# Sheet1.net
KiCad netlist of a schematic drawn in Altium Designer
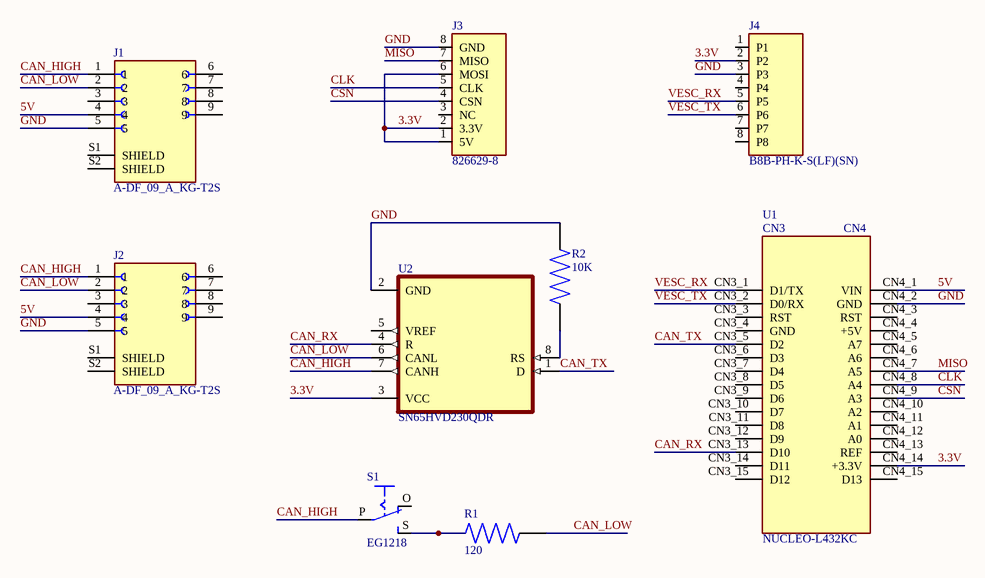
[diagram p0: Sheet1.SchDoc]

(export (version "E")
  (design (tool "Eeschema 10.0.6"))
  (components
    (comp (ref "J1")
      (value "A-DF_09_A_KG-T2S")
      (footprint "ASSMANN_A-DF_09_A_KG-T2S")
      (description "9 Position D-Sub Receptacle, Female Sockets Connector")
      (fields (field (name "MF") "Assmann WSW") (field (name "MP") "A-DF 09 A/KG-T2S"))
      (libsource (lib "A-DF_09_A_KG-T2S") (part "A-DF_09_A_KG-T2S"))
    )
    (comp (ref "J2")
      (value "A-DF_09_A_KG-T2S")
      (footprint "ASSMANN_A-DF_09_A_KG-T2S")
      (description "9 Position D-Sub Receptacle, Female Sockets Connector")
      (fields (field (name "MF") "Assmann WSW") (field (name "MP") "A-DF 09 A/KG-T2S"))
      (libsource (lib "A-DF_09_A_KG-T2S") (part "A-DF_09_A_KG-T2S"))
    )
    (comp (ref "J3")
      (value "826629-8")
      (footprint "TE_826629-8")
      (description "Conn Unshrouded Header HDR 8 POS 2.54mm Solder ST Thru-Hole Automotive Box")
      (fields (field (name "MF") "TE Connectivity"))
      (libsource (lib "826629-8") (part "826629-8"))
    )
    (comp (ref "J4")
      (value "B8B-PH-K-S(LF)(SN)")
      (footprint "SnapEDApcb:JST_B8B-PH-K-S(LF)(SN)")
      (description "Connector Header Through Hole 8 position 0.079 _2.00mm_")
      (fields (field (name "MF") "JST Sales") (field (name "MP") "B8B-PH-K-S_LF__SN_"))
      (libsource (lib "B8B-PH-K-S_LF__SN_") (part "B8B-PH-K-S(LF)(SN)"))
    )
    (comp (ref "R1")
      (value "120")
      (footprint "RESC3216X65N")
      (fields (field (name "MP") "KTR18EZPF9530"))
      (libsource (lib "KTR18EZPF9530") (part "KTR18EZPF9530"))
    )
    (comp (ref "R2")
      (value "10K")
      (footprint "RESC3216X65N")
      (fields (field (name "MP") "KTR18EZPF9530"))
      (libsource (lib "KTR18EZPF9530") (part "KTR18EZPF9530"))
    )
    (comp (ref "S1") (value "EG1218") (footprint "EG1218:EG1218") (libsource (lib "EG1218") (part "EG1218")))
    (comp (ref "U1")
      (value "NUCLEO-L432KC")
      (footprint "MODULE_NUCLEO-L432KC")
      (description "STM32 Nucleo-32 development board with STM32L432KC MCU, supports Arduino connectivity")
      (libsource (lib "NUCLEO-L432KC") (part "NUCLEO-L432KC"))
    )
    (comp (ref "U2")
      (value "SN65HVD230QDR")
      (footprint "SOIC127P599X175-8N")
      (description "3.3-V CAN Transceiver with Standby Mode 8-SOIC -40 to 125")
      (fields (field (name "MF") "Texas Instruments"))
      (libsource (lib "SN65HVD230QDR") (part "SN65HVD230QDR"))
    )
  )
  (nets
    (net (code "1") (name "/3.3V") (class "Default")
      (node (ref "J3") (pin "1") (pinfunction "5V_1") (pintype "passive"))
      (node (ref "J3") (pin "2") (pinfunction "3.3V_2") (pintype "passive"))
      (node (ref "J3") (pin "6") (pinfunction "MOSI_6") (pintype "passive"))
      (node (ref "J4") (pin "2") (pinfunction "P2_2") (pintype "passive"))
      (node (ref "U1") (pin "CN4_14") (pinfunction "+3.3V_CN4_14") (pintype "power_in"))
      (node (ref "U2") (pin "3") (pinfunction "VCC_3") (pintype "power_in"))
    )
    (net (code "2") (name "/5V") (class "Default")
      (node (ref "J1") (pin "4") (pinfunction "4_4") (pintype "passive"))
      (node (ref "J2") (pin "4") (pinfunction "4_4") (pintype "passive"))
      (node (ref "U1") (pin "CN4_1") (pinfunction "VIN_CN4_1") (pintype "power_in"))
    )
    (net (code "3") (name "/CAN_HIGH") (class "Default")
      (node (ref "J1") (pin "1") (pinfunction "1_1") (pintype "passive"))
      (node (ref "J2") (pin "1") (pinfunction "1_1") (pintype "passive"))
      (node (ref "S1") (pin "P") (pinfunction "P_P") (pintype "passive"))
      (node (ref "U2") (pin "7") (pinfunction "CANH_7") (pintype "output"))
    )
    (net (code "4") (name "/CAN_LOW") (class "Default")
      (node (ref "J1") (pin "2") (pinfunction "2_2") (pintype "passive"))
      (node (ref "J2") (pin "2") (pinfunction "2_2") (pintype "passive"))
      (node (ref "R1") (pin "2") (pinfunction "2_2") (pintype "passive"))
      (node (ref "U2") (pin "6") (pinfunction "CANL_6") (pintype "output"))
    )
    (net (code "5") (name "/CAN_RX") (class "Default")
      (node (ref "U1") (pin "CN3_13") (pinfunction "D10_CN3_13") (pintype "passive"))
      (node (ref "U2") (pin "4") (pinfunction "R_4") (pintype "output"))
    )
    (net (code "6") (name "/CAN_TX") (class "Default")
      (node (ref "U1") (pin "CN3_5") (pinfunction "D2_CN3_5") (pintype "power_in"))
      (node (ref "U2") (pin "1") (pinfunction "D_1") (pintype "input"))
    )
    (net (code "7") (name "/CLK") (class "Default")
      (node (ref "J3") (pin "5") (pinfunction "CLK_5") (pintype "passive"))
      (node (ref "U1") (pin "CN4_8") (pinfunction "A4_CN4_8") (pintype "passive"))
    )
    (net (code "8") (name "/CSN") (class "Default")
      (node (ref "J3") (pin "4") (pinfunction "CSN_4") (pintype "passive"))
      (node (ref "U1") (pin "CN4_9") (pinfunction "A3_CN4_9") (pintype "passive"))
    )
    (net (code "9") (name "/GND") (class "Default")
      (node (ref "J1") (pin "5") (pinfunction "5_5") (pintype "passive"))
      (node (ref "J2") (pin "5") (pinfunction "5_5") (pintype "passive"))
      (node (ref "J3") (pin "8") (pinfunction "GND_8") (pintype "passive"))
      (node (ref "J4") (pin "3") (pinfunction "P3_3") (pintype "passive"))
      (node (ref "R2") (pin "2") (pinfunction "2_2") (pintype "passive"))
      (node (ref "U1") (pin "CN4_2") (pinfunction "GND_CN4_2") (pintype "power_in"))
      (node (ref "U2") (pin "2") (pinfunction "GND_2") (pintype "power_in"))
    )
    (net (code "10") (name "/MISO") (class "Default")
      (node (ref "J3") (pin "7") (pinfunction "MISO_7") (pintype "passive"))
      (node (ref "U1") (pin "CN4_7") (pinfunction "A5_CN4_7") (pintype "passive"))
    )
    (net (code "11") (name "/VESC_RX") (class "Default")
      (node (ref "J4") (pin "5") (pinfunction "P5_5") (pintype "passive"))
      (node (ref "U1") (pin "CN3_1") (pinfunction "D1/TX_CN3_1") (pintype "power_in"))
    )
    (net (code "12") (name "/VESC_TX") (class "Default")
      (node (ref "J4") (pin "6") (pinfunction "P6_6") (pintype "passive"))
      (node (ref "U1") (pin "CN3_2") (pinfunction "D0/RX_CN3_2") (pintype "power_in"))
    )
    (net (code "13") (name "Net-(R1-Pad1)") (class "Default")
      (node (ref "R1") (pin "1") (pinfunction "1_1") (pintype "passive"))
      (node (ref "S1") (pin "S") (pinfunction "S_S") (pintype "passive"))
    )
    (net (code "14") (name "Net-(U2-RS)") (class "Default")
      (node (ref "R2") (pin "1") (pinfunction "1_1") (pintype "passive"))
      (node (ref "U2") (pin "8") (pinfunction "RS_8") (pintype "input"))
    )
    (net (code "15") (name "unconnected-(J1-Pad3)") (class "Default")
      (node (ref "J1") (pin "3") (pinfunction "3_3") (pintype "passive"))
    )
    (net (code "16") (name "unconnected-(J1-Pad6)") (class "Default")
      (node (ref "J1") (pin "6") (pinfunction "6_6") (pintype "passive"))
    )
    (net (code "17") (name "unconnected-(J1-Pad7)") (class "Default")
      (node (ref "J1") (pin "7") (pinfunction "7_7") (pintype "passive"))
    )
    (net (code "18") (name "unconnected-(J1-Pad8)") (class "Default")
      (node (ref "J1") (pin "8") (pinfunction "8_8") (pintype "passive"))
    )
    (net (code "19") (name "unconnected-(J1-Pad9)") (class "Default")
      (node (ref "J1") (pin "9") (pinfunction "9_9") (pintype "passive"))
    )
    (net (code "20") (name "unconnected-(J1-SHIELD-PadS1)") (class "Default")
      (node (ref "J1") (pin "S1") (pinfunction "SHIELD_S1") (pintype "passive"))
    )
    (net (code "21") (name "unconnected-(J1-SHIELD-PadS2)") (class "Default")
      (node (ref "J1") (pin "S2") (pinfunction "SHIELD_S2") (pintype "passive"))
    )
    (net (code "22") (name "unconnected-(J2-Pad3)") (class "Default")
      (node (ref "J2") (pin "3") (pinfunction "3_3") (pintype "passive"))
    )
    (net (code "23") (name "unconnected-(J2-Pad6)") (class "Default")
      (node (ref "J2") (pin "6") (pinfunction "6_6") (pintype "passive"))
    )
    (net (code "24") (name "unconnected-(J2-Pad7)") (class "Default")
      (node (ref "J2") (pin "7") (pinfunction "7_7") (pintype "passive"))
    )
    (net (code "25") (name "unconnected-(J2-Pad8)") (class "Default")
      (node (ref "J2") (pin "8") (pinfunction "8_8") (pintype "passive"))
    )
    (net (code "26") (name "unconnected-(J2-Pad9)") (class "Default")
      (node (ref "J2") (pin "9") (pinfunction "9_9") (pintype "passive"))
    )
    (net (code "27") (name "unconnected-(J2-SHIELD-PadS1)") (class "Default")
      (node (ref "J2") (pin "S1") (pinfunction "SHIELD_S1") (pintype "passive"))
    )
    (net (code "28") (name "unconnected-(J2-SHIELD-PadS2)") (class "Default")
      (node (ref "J2") (pin "S2") (pinfunction "SHIELD_S2") (pintype "passive"))
    )
    (net (code "29") (name "unconnected-(J3-NC-Pad3)") (class "Default")
      (node (ref "J3") (pin "3") (pinfunction "NC_3") (pintype "passive"))
    )
    (net (code "30") (name "unconnected-(J4-P1-Pad1)") (class "Default")
      (node (ref "J4") (pin "1") (pinfunction "P1_1") (pintype "passive"))
    )
    (net (code "31") (name "unconnected-(J4-P4-Pad4)") (class "Default")
      (node (ref "J4") (pin "4") (pinfunction "P4_4") (pintype "passive"))
    )
    (net (code "32") (name "unconnected-(J4-P7-Pad7)") (class "Default")
      (node (ref "J4") (pin "7") (pinfunction "P7_7") (pintype "passive"))
    )
    (net (code "33") (name "unconnected-(J4-P8-Pad8)") (class "Default")
      (node (ref "J4") (pin "8") (pinfunction "P8_8") (pintype "passive"))
    )
    (net (code "34") (name "unconnected-(S1-PadO)") (class "Default")
      (node (ref "S1") (pin "O") (pinfunction "O_O") (pintype "passive"))
    )
    (net (code "35") (name "unconnected-(U1-+5V-PadCN4_4)") (class "Default")
      (node (ref "U1") (pin "CN4_4") (pinfunction "+5V_CN4_4") (pintype "power_in"))
    )
    (net (code "36") (name "unconnected-(U1-A0-PadCN4_12)") (class "Default")
      (node (ref "U1") (pin "CN4_12") (pinfunction "A0_CN4_12") (pintype "passive"))
    )
    (net (code "37") (name "unconnected-(U1-A1-PadCN4_11)") (class "Default")
      (node (ref "U1") (pin "CN4_11") (pinfunction "A1_CN4_11") (pintype "passive"))
    )
    (net (code "38") (name "unconnected-(U1-A2-PadCN4_10)") (class "Default")
      (node (ref "U1") (pin "CN4_10") (pinfunction "A2_CN4_10") (pintype "passive"))
    )
    (net (code "39") (name "unconnected-(U1-A6-PadCN4_6)") (class "Default")
      (node (ref "U1") (pin "CN4_6") (pinfunction "A6_CN4_6") (pintype "passive"))
    )
    (net (code "40") (name "unconnected-(U1-A7-PadCN4_5)") (class "Default")
      (node (ref "U1") (pin "CN4_5") (pinfunction "A7_CN4_5") (pintype "passive"))
    )
    (net (code "41") (name "unconnected-(U1-D3-PadCN3_6)") (class "Default")
      (node (ref "U1") (pin "CN3_6") (pinfunction "D3_CN3_6") (pintype "power_in"))
    )
    (net (code "42") (name "unconnected-(U1-D4-PadCN3_7)") (class "Default")
      (node (ref "U1") (pin "CN3_7") (pinfunction "D4_CN3_7") (pintype "power_in"))
    )
    (net (code "43") (name "unconnected-(U1-D5-PadCN3_8)") (class "Default")
      (node (ref "U1") (pin "CN3_8") (pinfunction "D5_CN3_8") (pintype "power_in"))
    )
    (net (code "44") (name "unconnected-(U1-D6-PadCN3_9)") (class "Default")
      (node (ref "U1") (pin "CN3_9") (pinfunction "D6_CN3_9") (pintype "power_in"))
    )
    (net (code "45") (name "unconnected-(U1-D7-PadCN3_10)") (class "Default")
      (node (ref "U1") (pin "CN3_10") (pinfunction "D7_CN3_10") (pintype "power_in"))
    )
    (net (code "46") (name "unconnected-(U1-D8-PadCN3_11)") (class "Default")
      (node (ref "U1") (pin "CN3_11") (pinfunction "D8_CN3_11") (pintype "power_in"))
    )
    (net (code "47") (name "unconnected-(U1-D9-PadCN3_12)") (class "Default")
      (node (ref "U1") (pin "CN3_12") (pinfunction "D9_CN3_12") (pintype "power_in"))
    )
    (net (code "48") (name "unconnected-(U1-D11-PadCN3_14)") (class "Default")
      (node (ref "U1") (pin "CN3_14") (pinfunction "D11_CN3_14") (pintype "power_in"))
    )
    (net (code "49") (name "unconnected-(U1-D12-PadCN3_15)") (class "Default")
      (node (ref "U1") (pin "CN3_15") (pinfunction "D12_CN3_15") (pintype "power_in"))
    )
    (net (code "50") (name "unconnected-(U1-D13-PadCN4_15)") (class "Default")
      (node (ref "U1") (pin "CN4_15") (pinfunction "D13_CN4_15") (pintype "power_in"))
    )
    (net (code "51") (name "unconnected-(U1-GND-PadCN3_4)") (class "Default")
      (node (ref "U1") (pin "CN3_4") (pinfunction "GND_CN3_4") (pintype "power_in"))
    )
    (net (code "52") (name "unconnected-(U1-REF-PadCN4_13)") (class "Default")
      (node (ref "U1") (pin "CN4_13") (pinfunction "REF_CN4_13") (pintype "passive"))
    )
    (net (code "53") (name "unconnected-(U1-RST-PadCN3_3)") (class "Default")
      (node (ref "U1") (pin "CN3_3") (pinfunction "RST_CN3_3") (pintype "power_in"))
    )
    (net (code "54") (name "unconnected-(U1-RST-PadCN4_3)") (class "Default")
      (node (ref "U1") (pin "CN4_3") (pinfunction "RST_CN4_3") (pintype "passive"))
    )
    (net (code "55") (name "unconnected-(U2-VREF-Pad5)") (class "Default")
      (node (ref "U2") (pin "5") (pinfunction "VREF_5") (pintype "output"))
    )
  )
)
